# XM125_Breakout.net
KiCad netlist of a schematic drawn in EAGLE
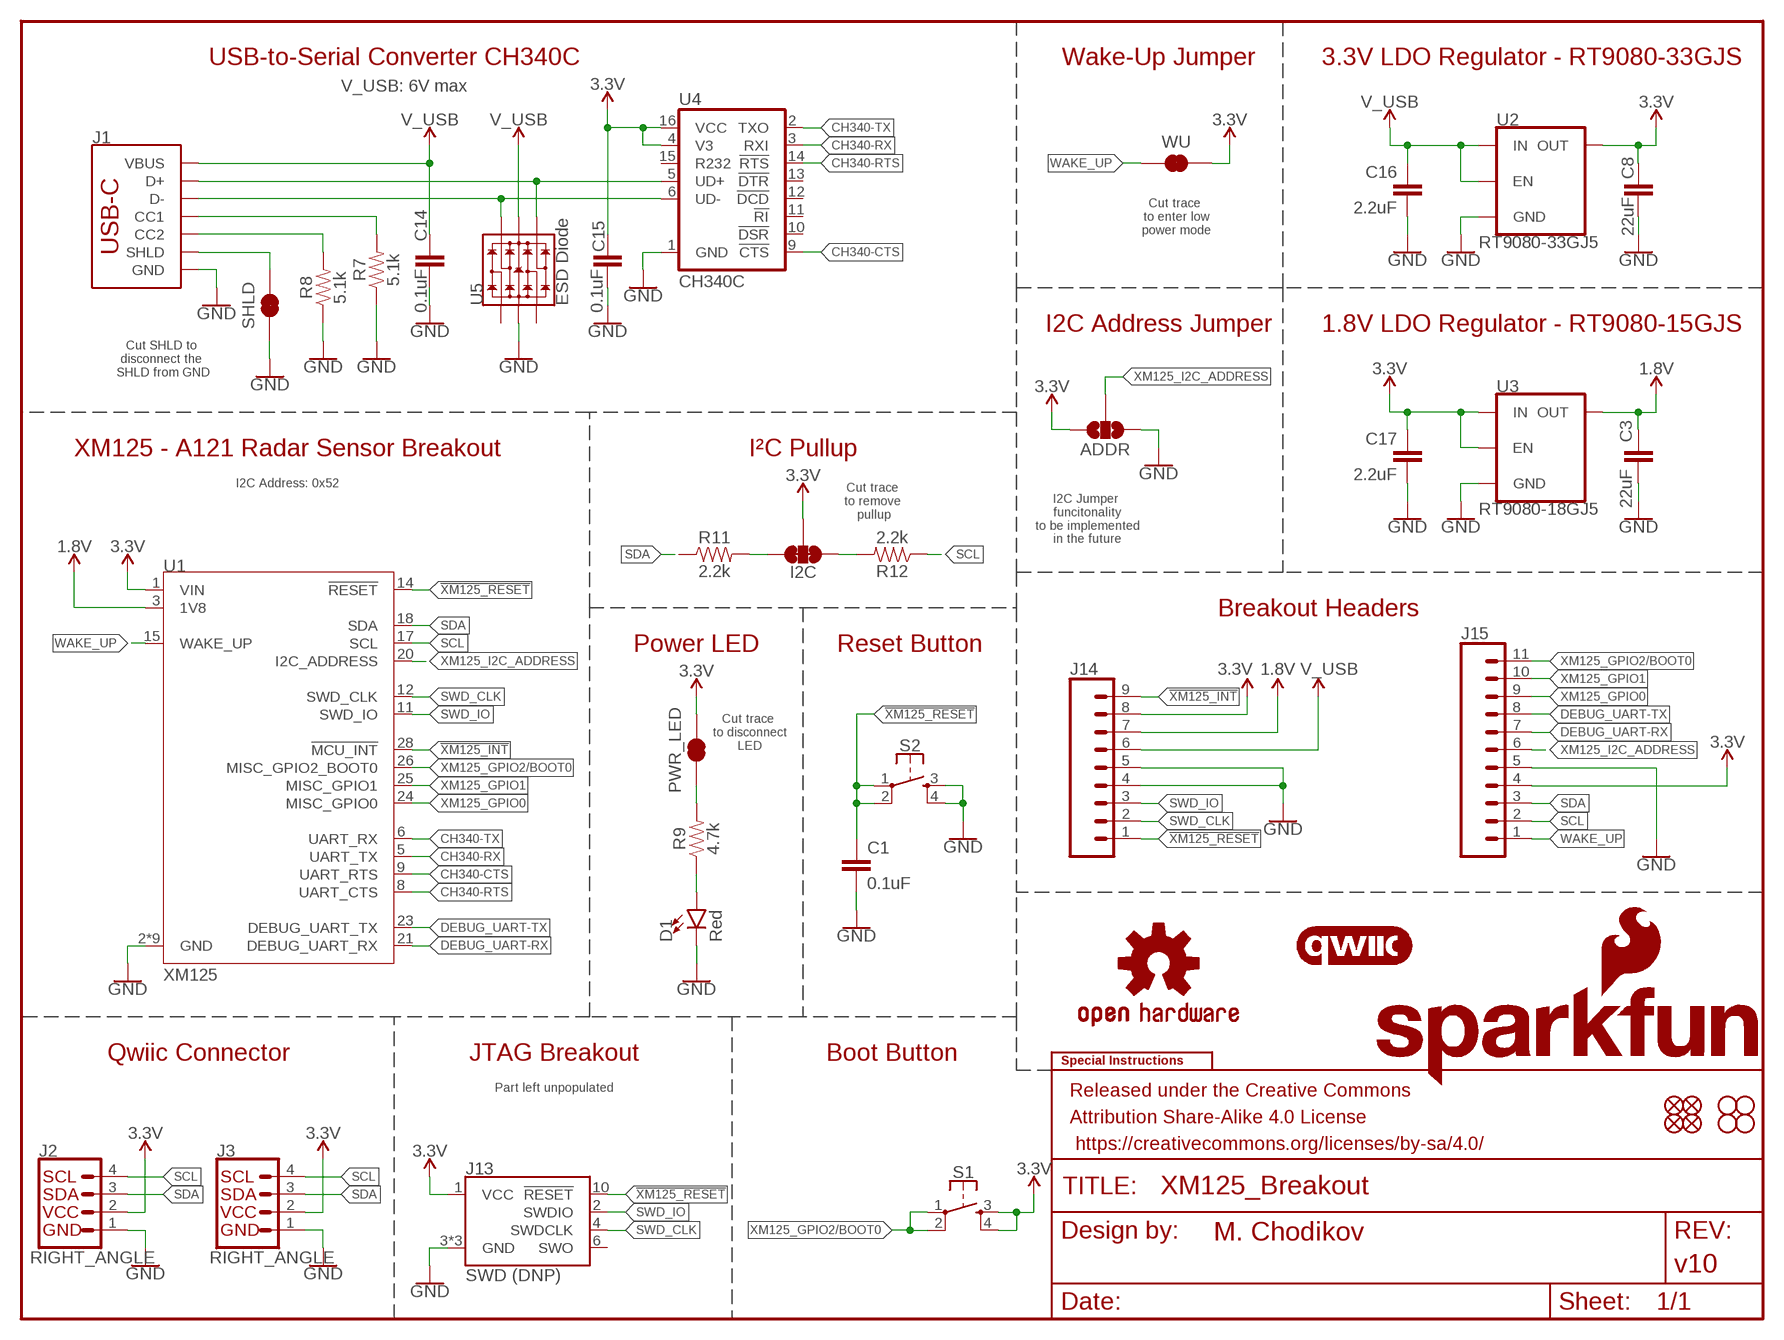
[diagram p0: schematic, sheet 1]

(export (version "E")
  (design (tool "Eeschema 10.0.6"))
  (components
    (comp (ref "ADDR")
      (value "JUMPER-SMT_3_NO_SILK")
      (footprint "eagle-import:SMT-JUMPER_3_NO_SILK")
      (libsource (lib "eagle-import") (part "JUMPER-SMT_3_NO_SILK"))
    )
    (comp (ref "C1")
      (value "0.1uF")
      (footprint "eagle-import:0603")
      (libsource (lib "eagle-import") (part "0.1UF-0603-25V-(+80/-20%)"))
    )
    (comp (ref "C3")
      (value "22uF")
      (footprint "eagle-import:0603")
      (libsource (lib "eagle-import") (part "22UF-0603-6.3V-20%"))
    )
    (comp (ref "C8")
      (value "22uF")
      (footprint "eagle-import:0603")
      (libsource (lib "eagle-import") (part "22UF-0603-6.3V-20%"))
    )
    (comp (ref "C14")
      (value "0.1uF")
      (footprint "eagle-import:0603")
      (libsource (lib "eagle-import") (part "0.1UF-0603-25V-(+80/-20%)"))
    )
    (comp (ref "C15")
      (value "0.1uF")
      (footprint "eagle-import:0603")
      (libsource (lib "eagle-import") (part "0.1UF-0603-25V-(+80/-20%)"))
    )
    (comp (ref "C16")
      (value "2.2uF")
      (footprint "eagle-import:0603")
      (libsource (lib "eagle-import") (part "2.2UF-0603-10V-20%"))
    )
    (comp (ref "C17")
      (value "2.2uF")
      (footprint "eagle-import:0603")
      (libsource (lib "eagle-import") (part "2.2UF-0603-10V-20%"))
    )
    (comp (ref "D1")
      (value "Red")
      (footprint "eagle-import:LED-0603")
      (libsource (lib "eagle-import") (part "LED-RED_0603-KB"))
    )
    (comp (ref "FD1")
      (value "FIDUCIAL1X2")
      (footprint "eagle-import:FIDUCIAL-1X2")
      (libsource (lib "eagle-import") (part "FIDUCIAL1X2"))
    )
    (comp (ref "FD2")
      (value "FIDUCIAL1X2")
      (footprint "eagle-import:FIDUCIAL-1X2")
      (libsource (lib "eagle-import") (part "FIDUCIAL1X2"))
    )
    (comp (ref "FD3")
      (value "FIDUCIAL1X2")
      (footprint "eagle-import:FIDUCIAL-1X2")
      (libsource (lib "eagle-import") (part "FIDUCIAL1X2"))
    )
    (comp (ref "FD4")
      (value "FIDUCIAL1X2")
      (footprint "eagle-import:FIDUCIAL-1X2")
      (libsource (lib "eagle-import") (part "FIDUCIAL1X2"))
    )
    (comp (ref "FRAME2")
      (value "FRAME-LETTER")
      (footprint "eagle-import:CREATIVE_COMMONS")
      (fields (field (name "DESIGNER") "M. Chodikov") (field (name "REV") "v10"))
      (libsource (lib "eagle-import") (part "FRAME-LETTER"))
    )
    (comp (ref "H1")
      (value "STAND-OFF")
      (footprint "eagle-import:STAND-OFF")
      (libsource (lib "eagle-import") (part "STAND-OFF"))
    )
    (comp (ref "H2")
      (value "STAND-OFF")
      (footprint "eagle-import:STAND-OFF")
      (libsource (lib "eagle-import") (part "STAND-OFF"))
    )
    (comp (ref "H3")
      (value "STAND-OFF")
      (footprint "eagle-import:STAND-OFF")
      (libsource (lib "eagle-import") (part "STAND-OFF"))
    )
    (comp (ref "H4")
      (value "STAND-OFF")
      (footprint "eagle-import:STAND-OFF")
      (libsource (lib "eagle-import") (part "STAND-OFF"))
    )
    (comp (ref "I2C")
      (value "JUMPER-SMT_3_2-NC_TRACE_SILK")
      (footprint "eagle-import:SMT-JUMPER_3_2-NC_TRACE_SILK")
      (libsource (lib "eagle-import") (part "JUMPER-SMT_3_2-NC_TRACE_SILK"))
    )
    (comp (ref "J1")
      (value "USB_C_2-LAYER_PADS")
      (footprint "eagle-import:USB-C-16P-2LAYER-PADS")
      (libsource (lib "eagle-import") (part "USB_C_2-LAYER_PADS"))
    )
    (comp (ref "J2")
      (value "RIGHT_ANGLE")
      (footprint "eagle-import:JST04_1MM_RA")
      (libsource (lib "eagle-import") (part "QWIIC_CONNECTORJS-1MM"))
    )
    (comp (ref "J3")
      (value "RIGHT_ANGLE")
      (footprint "eagle-import:JST04_1MM_RA")
      (libsource (lib "eagle-import") (part "QWIIC_CONNECTORJS-1MM"))
    )
    (comp (ref "J13")
      (value "SWD (DNP)")
      (footprint "eagle-import:2X5-SMD-UNSHROUDED_DNP_NO_PASTE")
      (libsource (lib "eagle-import") (part "CORTEX_JTAG_DEBUG_MINIMUM_SMD_UNSHROUDED_DNP_NO_PASTE"))
    )
    (comp (ref "J14")
      (value "CONN_09NO_SILK")
      (footprint "eagle-import:1X09_NO_SILK")
      (libsource (lib "eagle-import") (part "CONN_09NO_SILK"))
    )
    (comp (ref "J15")
      (value "CONN_111X11_NO_SILK")
      (footprint "eagle-import:1X11_NO_SILK")
      (libsource (lib "eagle-import") (part "CONN_111X11_NO_SILK"))
    )
    (comp (ref "LOGO1")
      (value "SPECIAL_INSTRUCTIONS-ORDERING")
      (footprint "eagle-import:ORDERING_INSTRUCTIONS")
      (libsource (lib "eagle-import") (part "SPECIAL_INSTRUCTIONS-ORDERING"))
    )
    (comp (ref "LOGO2")
      (value "QWIIC_LOGO_4MM")
      (footprint "eagle-import:QWIIC_4MM")
      (libsource (lib "eagle-import") (part "QWIIC_LOGO_4MM"))
    )
    (comp (ref "LOGO3")
      (value "SFE_LOGO_NAME_FLAME.1_INCH")
      (footprint "eagle-import:SFE_LOGO_NAME_FLAME_.1")
      (libsource (lib "eagle-import") (part "SFE_LOGO_NAME_FLAME.1_INCH"))
    )
    (comp (ref "LOGO4")
      (value "OSHW-LOGOS")
      (footprint "eagle-import:OSHW-LOGO-S")
      (libsource (lib "eagle-import") (part "OSHW-LOGOS"))
    )
    (comp (ref "LOGO5")
      (value "SFE_LOGO_FLAME.1_INCH")
      (footprint "eagle-import:SFE_LOGO_FLAME_.1")
      (libsource (lib "eagle-import") (part "SFE_LOGO_FLAME.1_INCH"))
    )
    (comp (ref "LOGO6")
      (value "SFE_LOGO_NAME_FLAME.1_INCH")
      (footprint "eagle-import:SFE_LOGO_NAME_FLAME_.1")
      (libsource (lib "eagle-import") (part "SFE_LOGO_NAME_FLAME.1_INCH"))
    )
    (comp (ref "PWR_LED")
      (value "JUMPER-SMT_2_NC_TRACE_SILK")
      (footprint "eagle-import:SMT-JUMPER_2_NC_TRACE_SILK")
      (libsource (lib "eagle-import") (part "JUMPER-SMT_2_NC_TRACE_SILK"))
    )
    (comp (ref "R7")
      (value "5.1k")
      (footprint "eagle-import:0603")
      (libsource (lib "eagle-import") (part "5.1KOHM5.1KOHM-0603-1/10W-1%"))
    )
    (comp (ref "R8")
      (value "5.1k")
      (footprint "eagle-import:0603")
      (libsource (lib "eagle-import") (part "5.1KOHM5.1KOHM-0603-1/10W-1%"))
    )
    (comp (ref "R9")
      (value "4.7k")
      (footprint "eagle-import:0603")
      (libsource (lib "eagle-import") (part "4.7KOHM-0603-1/10W-1%"))
    )
    (comp (ref "R11")
      (value "2.2k")
      (footprint "eagle-import:0603")
      (libsource (lib "eagle-import") (part "2.2KOHM-0603-1/10W-1%"))
    )
    (comp (ref "R12")
      (value "2.2k")
      (footprint "eagle-import:0603")
      (libsource (lib "eagle-import") (part "2.2KOHM-0603-1/10W-1%"))
    )
    (comp (ref "S1")
      (value "MOMENTARY-SWITCH-SPST-2-SMD-5.2MM")
      (footprint "eagle-import:TACTILE_SWITCH_SMD_5.2MM")
      (libsource (lib "eagle-import") (part "MOMENTARY-SWITCH-SPST-2-SMD-5.2MM"))
    )
    (comp (ref "S2")
      (value "MOMENTARY-SWITCH-SPST-2-SMD-5.2MM")
      (footprint "eagle-import:TACTILE_SWITCH_SMD_5.2MM")
      (libsource (lib "eagle-import") (part "MOMENTARY-SWITCH-SPST-2-SMD-5.2MM"))
    )
    (comp (ref "SHLD")
      (value "JUMPER-SMT_2_NC_TRACE_SILK")
      (footprint "eagle-import:SMT-JUMPER_2_NC_TRACE_SILK")
      (libsource (lib "eagle-import") (part "JUMPER-SMT_2_NC_TRACE_SILK"))
    )
    (comp (ref "U1")
      (value "XM125")
      (footprint "eagle-import:XM125_ACC")
      (libsource (lib "eagle-import") (part "XM125"))
    )
    (comp (ref "U2")
      (value "RT9080-33GJ5")
      (footprint "eagle-import:SOT23-5")
      (libsource (lib "eagle-import") (part "V_REG_RT9080"))
    )
    (comp (ref "U3")
      (value "RT9080-18GJ5")
      (footprint "eagle-import:SOT23-5")
      (libsource (lib "eagle-import") (part "RT9080-18GJ5"))
    )
    (comp (ref "U4")
      (value "CH340C")
      (footprint "eagle-import:SO016")
      (libsource (lib "eagle-import") (part "CH340C"))
    )
    (comp (ref "U5")
      (value "ESD Diode")
      (footprint "eagle-import:SOT-23-6")
      (libsource (lib "eagle-import") (part "TVS_DIODE_ARRAY_DT1042-04SO-7"))
    )
    (comp (ref "WU")
      (value "JUMPER-SMT_2_NC_TRACE_SILK")
      (footprint "eagle-import:SMT-JUMPER_2_NC_TRACE_SILK")
      (libsource (lib "eagle-import") (part "JUMPER-SMT_2_NC_TRACE_SILK"))
    )
  )
  (nets
    (net (code "1") (name "/~{XM125_INT}") (class "Default")
      (node (ref "J14") (pin "9") (pinfunction "9_9") (pintype "passive"))
      (node (ref "U1") (pin "28") (pinfunction "~{MCU_INT}_28") (pintype "passive"))
    )
    (net (code "2") (name "/~{XM125_RESET}") (class "Default")
      (node (ref "C1") (pin "2") (pinfunction "2_2") (pintype "passive"))
      (node (ref "J13") (pin "10") (pinfunction "~{RESET}_10") (pintype "bidirectional"))
      (node (ref "J14") (pin "1") (pinfunction "1_1") (pintype "passive"))
      (node (ref "S2") (pin "1") (pinfunction "1_1") (pintype "passive"))
      (node (ref "S2") (pin "2") (pinfunction "2_2") (pintype "passive"))
      (node (ref "U1") (pin "14") (pinfunction "~{RESET}_14") (pintype "passive"))
    )
    (net (code "3") (name "1.8V") (class "Default")
      (node (ref "C3") (pin "1") (pinfunction "1_1") (pintype "passive"))
      (node (ref "J14") (pin "7") (pinfunction "7_7") (pintype "passive"))
      (node (ref "U1") (pin "3") (pinfunction "1V8_3") (pintype "power_in"))
      (node (ref "U3") (pin "5") (pinfunction "OUT_5") (pintype "passive"))
    )
    (net (code "4") (name "3.3V") (class "Default")
      (node (ref "ADDR") (pin "3") (pinfunction "3_3") (pintype "passive"))
      (node (ref "C15") (pin "1") (pinfunction "1_1") (pintype "passive"))
      (node (ref "C17") (pin "1") (pinfunction "1_1") (pintype "passive"))
      (node (ref "C8") (pin "1") (pinfunction "1_1") (pintype "passive"))
      (node (ref "I2C") (pin "2") (pinfunction "2_2") (pintype "passive"))
      (node (ref "J13") (pin "1") (pinfunction "VCC_1") (pintype "bidirectional"))
      (node (ref "J14") (pin "8") (pinfunction "8_8") (pintype "passive"))
      (node (ref "J15") (pin "4") (pinfunction "4_4") (pintype "passive"))
      (node (ref "J2") (pin "2") (pinfunction "2_2") (pintype "power_in"))
      (node (ref "J3") (pin "2") (pinfunction "2_2") (pintype "power_in"))
      (node (ref "PWR_LED") (pin "2") (pinfunction "2_2") (pintype "passive"))
      (node (ref "S1") (pin "3") (pinfunction "3_3") (pintype "passive"))
      (node (ref "S1") (pin "4") (pinfunction "4_4") (pintype "passive"))
      (node (ref "U1") (pin "1") (pinfunction "VIN_1") (pintype "power_in"))
      (node (ref "U2") (pin "5") (pinfunction "OUT_5") (pintype "passive"))
      (node (ref "U3") (pin "1") (pinfunction "IN_1") (pintype "input"))
      (node (ref "U3") (pin "3") (pinfunction "EN_3") (pintype "input"))
      (node (ref "U4") (pin "16") (pinfunction "VCC_16") (pintype "bidirectional"))
      (node (ref "U4") (pin "4") (pinfunction "V3_4") (pintype "bidirectional"))
      (node (ref "WU") (pin "2") (pinfunction "2_2") (pintype "passive"))
    )
    (net (code "5") (name "CH340-CTS") (class "Default")
      (node (ref "U1") (pin "9") (pinfunction "UART_RTS_9") (pintype "passive"))
      (node (ref "U4") (pin "9") (pinfunction "~{CTS}_9") (pintype "bidirectional"))
    )
    (net (code "6") (name "CH340-RTS") (class "Default")
      (node (ref "U1") (pin "8") (pinfunction "UART_CTS_8") (pintype "passive"))
      (node (ref "U4") (pin "14") (pinfunction "~{RTS}_14") (pintype "bidirectional"))
    )
    (net (code "7") (name "CH340-RX") (class "Default")
      (node (ref "U1") (pin "5") (pinfunction "UART_TX_5") (pintype "passive"))
      (node (ref "U4") (pin "3") (pinfunction "RXI_3") (pintype "bidirectional"))
    )
    (net (code "8") (name "CH340-TX") (class "Default")
      (node (ref "U1") (pin "6") (pinfunction "UART_RX_6") (pintype "passive"))
      (node (ref "U4") (pin "2") (pinfunction "TXO_2") (pintype "bidirectional"))
    )
    (net (code "9") (name "DEBUG_UART-RX") (class "Default")
      (node (ref "J15") (pin "7") (pinfunction "7_7") (pintype "passive"))
      (node (ref "U1") (pin "21") (pinfunction "DEBUG_UART_RX_21") (pintype "passive"))
    )
    (net (code "10") (name "DEBUG_UART-TX") (class "Default")
      (node (ref "J15") (pin "8") (pinfunction "8_8") (pintype "passive"))
      (node (ref "U1") (pin "23") (pinfunction "DEBUG_UART_TX_23") (pintype "passive"))
    )
    (net (code "11") (name "GND") (class "Default")
      (node (ref "ADDR") (pin "1") (pinfunction "1_1") (pintype "passive"))
      (node (ref "C1") (pin "1") (pinfunction "1_1") (pintype "passive"))
      (node (ref "C14") (pin "2") (pinfunction "2_2") (pintype "passive"))
      (node (ref "C15") (pin "2") (pinfunction "2_2") (pintype "passive"))
      (node (ref "C16") (pin "2") (pinfunction "2_2") (pintype "passive"))
      (node (ref "C17") (pin "2") (pinfunction "2_2") (pintype "passive"))
      (node (ref "C3") (pin "2") (pinfunction "2_2") (pintype "passive"))
      (node (ref "C8") (pin "2") (pinfunction "2_2") (pintype "passive"))
      (node (ref "D1") (pin "C") (pinfunction "C_C") (pintype "passive"))
      (node (ref "J1") (pin "GND") (pinfunction "GND_GND") (pintype "bidirectional"))
      (node (ref "J1") (pin "GND2") (pinfunction "GND_GND2") (pintype "bidirectional"))
      (node (ref "J13") (pin "3") (pinfunction "GND_3") (pintype "bidirectional"))
      (node (ref "J13") (pin "5") (pinfunction "GND_5") (pintype "bidirectional"))
      (node (ref "J13") (pin "9") (pinfunction "GND_9") (pintype "bidirectional"))
      (node (ref "J14") (pin "4") (pinfunction "4_4") (pintype "passive"))
      (node (ref "J14") (pin "5") (pinfunction "5_5") (pintype "passive"))
      (node (ref "J15") (pin "5") (pinfunction "5_5") (pintype "passive"))
      (node (ref "J2") (pin "1") (pinfunction "1_1") (pintype "power_in"))
      (node (ref "J3") (pin "1") (pinfunction "1_1") (pintype "power_in"))
      (node (ref "R7") (pin "1") (pinfunction "1_1") (pintype "passive"))
      (node (ref "R8") (pin "1") (pinfunction "1_1") (pintype "passive"))
      (node (ref "S2") (pin "3") (pinfunction "3_3") (pintype "passive"))
      (node (ref "S2") (pin "4") (pinfunction "4_4") (pintype "passive"))
      (node (ref "SHLD") (pin "1") (pinfunction "1_1") (pintype "passive"))
      (node (ref "U1") (pin "10") (pinfunction "GND_10") (pintype "passive"))
      (node (ref "U1") (pin "13") (pinfunction "GND_13") (pintype "passive"))
      (node (ref "U1") (pin "16") (pinfunction "GND_16") (pintype "passive"))
      (node (ref "U1") (pin "19") (pinfunction "GND_19") (pintype "passive"))
      (node (ref "U1") (pin "2") (pinfunction "GND_2") (pintype "passive"))
      (node (ref "U1") (pin "22") (pinfunction "GND_22") (pintype "passive"))
      (node (ref "U1") (pin "27") (pinfunction "GND_27") (pintype "passive"))
      (node (ref "U1") (pin "4") (pinfunction "GND_4") (pintype "passive"))
      (node (ref "U1") (pin "7") (pinfunction "GND_7") (pintype "passive"))
      (node (ref "U2") (pin "2") (pinfunction "GND_2") (pintype "input"))
      (node (ref "U3") (pin "2") (pinfunction "GND_2") (pintype "input"))
      (node (ref "U4") (pin "1") (pinfunction "GND_1") (pintype "bidirectional"))
      (node (ref "U5") (pin "2") (pinfunction "VSS_2") (pintype "bidirectional"))
    )
    (net (code "12") (name "Net-(D1-PadA)") (class "Default")
      (node (ref "D1") (pin "A") (pinfunction "A_A") (pintype "passive"))
      (node (ref "R9") (pin "1") (pinfunction "1_1") (pintype "passive"))
    )
    (net (code "13") (name "Net-(I2C-Pad1)") (class "Default")
      (node (ref "I2C") (pin "1") (pinfunction "1_1") (pintype "passive"))
      (node (ref "R12") (pin "2") (pinfunction "2_2") (pintype "passive"))
    )
    (net (code "14") (name "Net-(I2C-Pad3)") (class "Default")
      (node (ref "I2C") (pin "3") (pinfunction "3_3") (pintype "passive"))
      (node (ref "R11") (pin "2") (pinfunction "2_2") (pintype "passive"))
    )
    (net (code "15") (name "Net-(J1-CC1)") (class "Default")
      (node (ref "J1") (pin "A5") (pinfunction "CC1_A5") (pintype "bidirectional"))
      (node (ref "R7") (pin "2") (pinfunction "2_2") (pintype "passive"))
    )
    (net (code "16") (name "Net-(J1-CC2)") (class "Default")
      (node (ref "J1") (pin "B5") (pinfunction "CC2_B5") (pintype "bidirectional"))
      (node (ref "R8") (pin "2") (pinfunction "2_2") (pintype "passive"))
    )
    (net (code "17") (name "Net-(J1-SHLD-PadSHLD1)") (class "Default")
      (node (ref "J1") (pin "SHLD1") (pinfunction "SHLD_SHLD1") (pintype "bidirectional"))
      (node (ref "J1") (pin "SHLD2") (pinfunction "SHLD_SHLD2") (pintype "bidirectional"))
      (node (ref "J1") (pin "SHLD3") (pinfunction "SHLD_SHLD3") (pintype "bidirectional"))
      (node (ref "J1") (pin "SHLD4") (pinfunction "SHLD_SHLD4") (pintype "bidirectional"))
      (node (ref "SHLD") (pin "2") (pinfunction "2_2") (pintype "passive"))
    )
    (net (code "18") (name "Net-(PWR_LED-Pad1)") (class "Default")
      (node (ref "PWR_LED") (pin "1") (pinfunction "1_1") (pintype "passive"))
      (node (ref "R9") (pin "2") (pinfunction "2_2") (pintype "passive"))
    )
    (net (code "19") (name "Net-(U4-UD+)") (class "Default")
      (node (ref "J1") (pin "A6") (pinfunction "D+_A6") (pintype "bidirectional"))
      (node (ref "J1") (pin "B6") (pinfunction "D+_B6") (pintype "bidirectional"))
      (node (ref "U4") (pin "5") (pinfunction "UD+_5") (pintype "bidirectional"))
      (node (ref "U5") (pin "4") (pinfunction "IO3_4") (pintype "bidirectional"))
    )
    (net (code "20") (name "Net-(U4-UD-)") (class "Default")
      (node (ref "J1") (pin "A7") (pinfunction "D-_A7") (pintype "bidirectional"))
      (node (ref "J1") (pin "B7") (pinfunction "D-_B7") (pintype "bidirectional"))
      (node (ref "U4") (pin "6") (pinfunction "UD-_6") (pintype "bidirectional"))
      (node (ref "U5") (pin "6") (pinfunction "IO4_6") (pintype "bidirectional"))
    )
    (net (code "21") (name "SCL") (class "Default")
      (node (ref "J15") (pin "2") (pinfunction "2_2") (pintype "passive"))
      (node (ref "J2") (pin "4") (pinfunction "4_4") (pintype "passive"))
      (node (ref "J3") (pin "4") (pinfunction "4_4") (pintype "passive"))
      (node (ref "R12") (pin "1") (pinfunction "1_1") (pintype "passive"))
      (node (ref "U1") (pin "17") (pinfunction "SCL_17") (pintype "passive"))
    )
    (net (code "22") (name "SDA") (class "Default")
      (node (ref "J15") (pin "3") (pinfunction "3_3") (pintype "passive"))
      (node (ref "J2") (pin "3") (pinfunction "3_3") (pintype "passive"))
      (node (ref "J3") (pin "3") (pinfunction "3_3") (pintype "passive"))
      (node (ref "R11") (pin "1") (pinfunction "1_1") (pintype "passive"))
      (node (ref "U1") (pin "18") (pinfunction "SDA_18") (pintype "passive"))
    )
    (net (code "23") (name "SWD_CLK") (class "Default")
      (node (ref "J13") (pin "4") (pinfunction "SWDCLK_4") (pintype "bidirectional"))
      (node (ref "J14") (pin "2") (pinfunction "2_2") (pintype "passive"))
      (node (ref "U1") (pin "12") (pinfunction "SWD_CLK_12") (pintype "passive"))
    )
    (net (code "24") (name "SWD_IO") (class "Default")
      (node (ref "J13") (pin "2") (pinfunction "SWDIO_2") (pintype "bidirectional"))
      (node (ref "J14") (pin "3") (pinfunction "3_3") (pintype "passive"))
      (node (ref "U1") (pin "11") (pinfunction "SWD_IO_11") (pintype "passive"))
    )
    (net (code "25") (name "V_USB") (class "Default")
      (node (ref "C14") (pin "1") (pinfunction "1_1") (pintype "passive"))
      (node (ref "C16") (pin "1") (pinfunction "1_1") (pintype "passive"))
      (node (ref "J1") (pin "VBUS1") (pinfunction "VBUS_VBUS1") (pintype "bidirectional"))
      (node (ref "J1") (pin "VBUS2") (pinfunction "VBUS_VBUS2") (pintype "bidirectional"))
      (node (ref "J14") (pin "6") (pinfunction "6_6") (pintype "passive"))
      (node (ref "U2") (pin "1") (pinfunction "IN_1") (pintype "input"))
      (node (ref "U2") (pin "3") (pinfunction "EN_3") (pintype "input"))
      (node (ref "U5") (pin "5") (pinfunction "VCC_5") (pintype "bidirectional"))
    )
    (net (code "26") (name "WAKE_UP") (class "Default")
      (node (ref "J15") (pin "1") (pinfunction "1_1") (pintype "passive"))
      (node (ref "U1") (pin "15") (pinfunction "WAKE_UP_15") (pintype "passive"))
      (node (ref "WU") (pin "1") (pinfunction "1_1") (pintype "passive"))
    )
    (net (code "27") (name "XM125_GPIO0") (class "Default")
      (node (ref "J15") (pin "9") (pinfunction "9_9") (pintype "passive"))
      (node (ref "U1") (pin "24") (pinfunction "MISC_GPIO0_24") (pintype "bidirectional"))
    )
    (net (code "28") (name "XM125_GPIO1") (class "Default")
      (node (ref "J15") (pin "10") (pinfunction "10_10") (pintype "passive"))
      (node (ref "U1") (pin "25") (pinfunction "MISC_GPIO1_25") (pintype "bidirectional"))
    )
    (net (code "29") (name "XM125_GPIO2{slash}BOOT0") (class "Default")
      (node (ref "J15") (pin "11") (pinfunction "11_11") (pintype "passive"))
      (node (ref "S1") (pin "1") (pinfunction "1_1") (pintype "passive"))
      (node (ref "S1") (pin "2") (pinfunction "2_2") (pintype "passive"))
      (node (ref "U1") (pin "26") (pinfunction "MISC_GPIO2_BOOT0_26") (pintype "bidirectional"))
    )
    (net (code "30") (name "XM125_I2C_ADDRESS") (class "Default")
      (node (ref "ADDR") (pin "2") (pinfunction "2_2") (pintype "passive"))
      (node (ref "J15") (pin "6") (pinfunction "6_6") (pintype "passive"))
      (node (ref "U1") (pin "20") (pinfunction "I2C_ADDRESS_20") (pintype "passive"))
    )
    (net (code "31") (name "unconnected-(J13-SWO-Pad6)") (class "Default")
      (node (ref "J13") (pin "6") (pinfunction "SWO_6") (pintype "bidirectional"))
    )
    (net (code "32") (name "unconnected-(U4-R232-Pad15)") (class "Default")
      (node (ref "U4") (pin "15") (pinfunction "R232_15") (pintype "bidirectional"))
    )
    (net (code "33") (name "unconnected-(U4-~{DCD}-Pad12)") (class "Default")
      (node (ref "U4") (pin "12") (pinfunction "~{DCD}_12") (pintype "bidirectional"))
    )
    (net (code "34") (name "unconnected-(U4-~{DSR}-Pad10)") (class "Default")
      (node (ref "U4") (pin "10") (pinfunction "~{DSR}_10") (pintype "bidirectional"))
    )
    (net (code "35") (name "unconnected-(U4-~{DTR}-Pad13)") (class "Default")
      (node (ref "U4") (pin "13") (pinfunction "~{DTR}_13") (pintype "bidirectional"))
    )
    (net (code "36") (name "unconnected-(U4-~{RI}-Pad11)") (class "Default")
      (node (ref "U4") (pin "11") (pinfunction "~{RI}_11") (pintype "bidirectional"))
    )
    (net (code "37") (name "unconnected-(U5-IO1-Pad1)") (class "Default")
      (node (ref "U5") (pin "1") (pinfunction "IO1_1") (pintype "bidirectional"))
    )
    (net (code "38") (name "unconnected-(U5-IO2-Pad3)") (class "Default")
      (node (ref "U5") (pin "3") (pinfunction "IO2_3") (pintype "bidirectional"))
    )
  )
)
